# samd21_sensorhub_1_2_5_dec2023.net
KiCad netlist of a schematic drawn in EAGLE
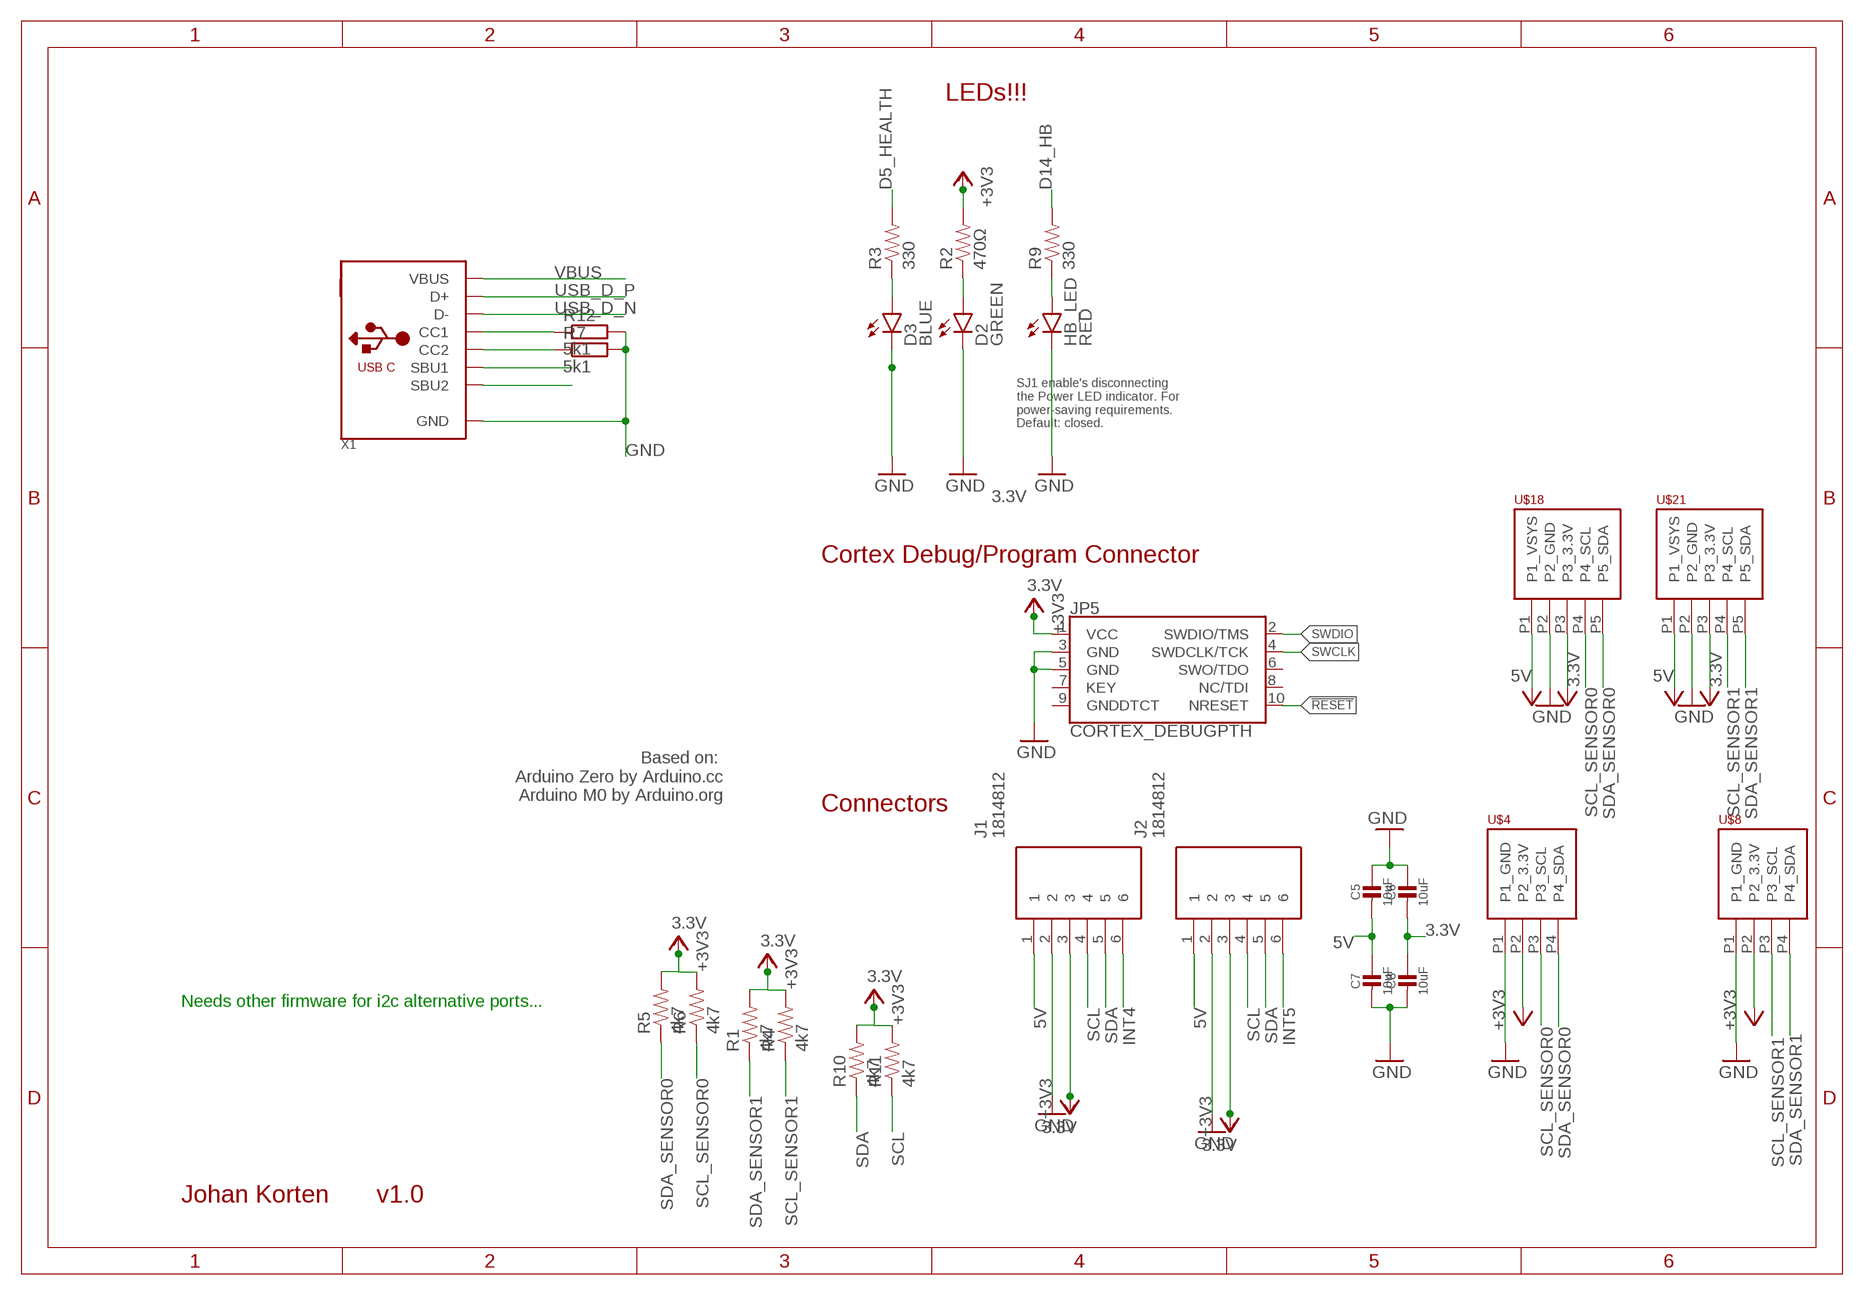
[diagram p0: schematic, sheet 1]
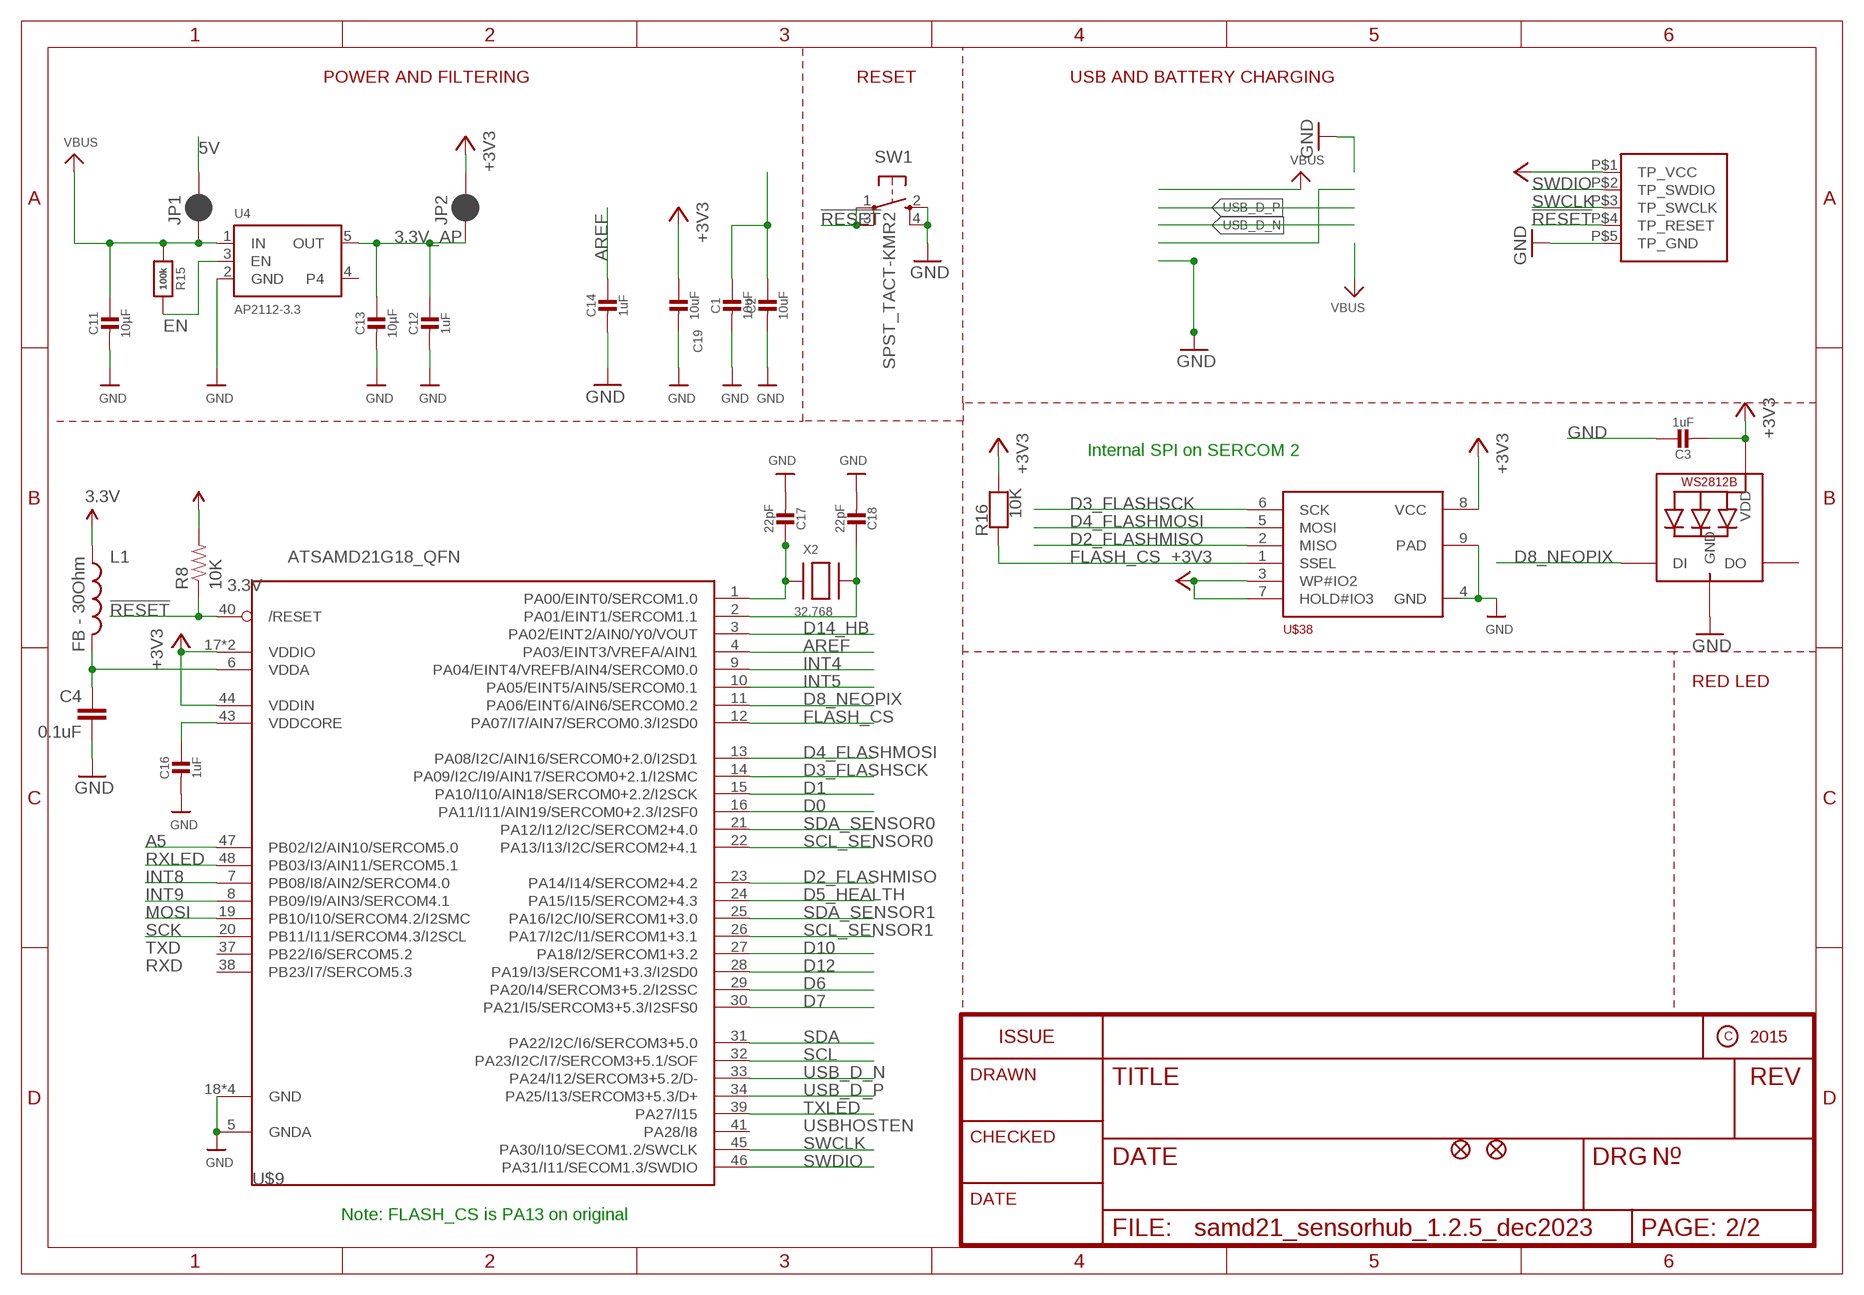
[diagram p1: schematic, sheet 2]

(export (version "E")
  (design (tool "Eeschema 10.0.6"))
  (components
    (comp (ref "C5")
      (value "10uF")
      (footprint "eagle-import:0805-NO")
      (libsource (lib "eagle-import") (part "CAP_CERAMIC0805-NOOUTLINE"))
    )
    (comp (ref "C6")
      (value "10uF")
      (footprint "eagle-import:0805-NO")
      (libsource (lib "eagle-import") (part "CAP_CERAMIC0805-NOOUTLINE"))
    )
    (comp (ref "C7")
      (value "10uF")
      (footprint "eagle-import:0805-NO")
      (libsource (lib "eagle-import") (part "CAP_CERAMIC0805-NOOUTLINE"))
    )
    (comp (ref "C8")
      (value "10uF")
      (footprint "eagle-import:0805-NO")
      (libsource (lib "eagle-import") (part "CAP_CERAMIC0805-NOOUTLINE"))
    )
    (comp (ref "D2")
      (value "GREEN")
      (footprint "eagle-import:LED-0603")
      (libsource (lib "eagle-import") (part "LED-RED0603"))
    )
    (comp (ref "D3")
      (value "BLUE")
      (footprint "eagle-import:LED-0603")
      (libsource (lib "eagle-import") (part "LED-BLUE0603"))
    )
    (comp (ref "HB_LED")
      (value "RED")
      (footprint "eagle-import:LED-0603")
      (libsource (lib "eagle-import") (part "LED-RED0603"))
    )
    (comp (ref "J1")
      (value "1814812")
      (footprint "eagle-import:1814812")
      (fields (field (name "MOUSER_PART_NUMBER") "651-1814812"))
      (libsource (lib "eagle-import") (part "1814812"))
    )
    (comp (ref "J2")
      (value "1814812")
      (footprint "eagle-import:1814812")
      (fields (field (name "MOUSER_PART_NUMBER") "651-1814812"))
      (libsource (lib "eagle-import") (part "1814812"))
    )
    (comp (ref "JP5")
      (value "CORTEX_DEBUGPTH")
      (footprint "eagle-import:2X5-PTH-1.27MM")
      (libsource (lib "eagle-import") (part "CORTEX_DEBUGPTH"))
    )
    (comp (ref "R1")
      (value "4k7")
      (footprint "eagle-import:0603-RES")
      (libsource (lib "eagle-import") (part "330OHM1/10W1%(0603)"))
    )
    (comp (ref "R2")
      (value "470Ω")
      (footprint "eagle-import:0603-RES")
      (libsource (lib "eagle-import") (part "330OHM1/10W1%(0603)"))
    )
    (comp (ref "R3")
      (value "330")
      (footprint "eagle-import:0603-RES")
      (libsource (lib "eagle-import") (part "330OHM1/10W1%(0603)"))
    )
    (comp (ref "R4")
      (value "4k7")
      (footprint "eagle-import:0603-RES")
      (libsource (lib "eagle-import") (part "330OHM1/10W1%(0603)"))
    )
    (comp (ref "R5")
      (value "4k7")
      (footprint "eagle-import:0603-RES")
      (libsource (lib "eagle-import") (part "330OHM1/10W1%(0603)"))
    )
    (comp (ref "R6")
      (value "4k7")
      (footprint "eagle-import:0603-RES")
      (libsource (lib "eagle-import") (part "330OHM1/10W1%(0603)"))
    )
    (comp (ref "R7")
      (value "5k1")
      (footprint "eagle-import:R0603")
      (libsource (lib "eagle-import") (part "R-EU_R0603"))
    )
    (comp (ref "R9")
      (value "330")
      (footprint "eagle-import:0603-RES")
      (libsource (lib "eagle-import") (part "330OHM1/10W1%(0603)"))
    )
    (comp (ref "R10")
      (value "4k7")
      (footprint "eagle-import:0603-RES")
      (libsource (lib "eagle-import") (part "330OHM1/10W1%(0603)"))
    )
    (comp (ref "R11")
      (value "4k7")
      (footprint "eagle-import:0603-RES")
      (libsource (lib "eagle-import") (part "330OHM1/10W1%(0603)"))
    )
    (comp (ref "R12")
      (value "5k1")
      (footprint "eagle-import:R0603")
      (libsource (lib "eagle-import") (part "R-EU_R0603"))
    )
    (comp (ref "U$4")
      (value "PHOENIX_PTSM_M4_THANGLE")
      (footprint "eagle-import:PTSM_M4_TH")
      (libsource (lib "eagle-import") (part "PHOENIX_PTSM_M4_THANGLE"))
    )
    (comp (ref "U$8")
      (value "PHOENIX_PTSM_M4_THANGLE")
      (footprint "eagle-import:PTSM_M4_TH")
      (libsource (lib "eagle-import") (part "PHOENIX_PTSM_M4_THANGLE"))
    )
    (comp (ref "U$18")
      (value "PHOENIX_PTSM_M5_TH_I2C++")
      (footprint "eagle-import:PTSM_M5_THRHOLE")
      (libsource (lib "eagle-import") (part "PHOENIX_PTSM_M5_TH_I2C++"))
    )
    (comp (ref "U$21")
      (value "PHOENIX_PTSM_M5_TH_I2C++")
      (footprint "eagle-import:PTSM_M5_THRHOLE")
      (libsource (lib "eagle-import") (part "PHOENIX_PTSM_M5_TH_I2C++"))
    )
    (comp (ref "X1")
      (value "USB_C")
      (footprint "eagle-import:USB_C_CUSB31-CFM2AX-01-X")
      (libsource (lib "eagle-import") (part "USB_C"))
    )
    (comp (ref "C1")
      (value "10uF")
      (footprint "eagle-import:0805-NO")
      (libsource (lib "eagle-import") (part "CAP_CERAMIC0805-NOOUTLINE"))
    )
    (comp (ref "C2")
      (value "10uF")
      (footprint "eagle-import:0805-NO")
      (libsource (lib "eagle-import") (part "CAP_CERAMIC0805-NOOUTLINE"))
    )
    (comp (ref "C3")
      (value "1uF")
      (footprint "eagle-import:0603-NO")
      (libsource (lib "eagle-import") (part "CAP_CERAMIC0603_NO"))
    )
    (comp (ref "C4")
      (value "0.1uF")
      (footprint "eagle-import:0402-CAP")
      (libsource (lib "eagle-import") (part "0.1UF-16V(+-10%)(0402)"))
    )
    (comp (ref "C11")
      (value "10µF")
      (footprint "eagle-import:0805-NO")
      (libsource (lib "eagle-import") (part "CAP_CERAMIC0805-NOOUTLINE"))
    )
    (comp (ref "C12")
      (value "1uF")
      (footprint "eagle-import:0603-NO")
      (libsource (lib "eagle-import") (part "CAP_CERAMIC0603_NO"))
    )
    (comp (ref "C13")
      (value "10µF")
      (footprint "eagle-import:0805-NO")
      (libsource (lib "eagle-import") (part "CAP_CERAMIC0805-NOOUTLINE"))
    )
    (comp (ref "C14")
      (value "1uF")
      (footprint "eagle-import:0603-NO")
      (libsource (lib "eagle-import") (part "CAP_CERAMIC0603_NO"))
    )
    (comp (ref "C16")
      (value "1uF")
      (footprint "eagle-import:0603-NO")
      (libsource (lib "eagle-import") (part "CAP_CERAMIC0603_NO"))
    )
    (comp (ref "C17")
      (value "22pF")
      (footprint "eagle-import:0603-NO")
      (libsource (lib "eagle-import") (part "CAP_CERAMIC0603_NO"))
    )
    (comp (ref "C18")
      (value "22pF")
      (footprint "eagle-import:0603-NO")
      (libsource (lib "eagle-import") (part "CAP_CERAMIC0603_NO"))
    )
    (comp (ref "C19")
      (value "10uF")
      (footprint "eagle-import:0805-NO")
      (libsource (lib "eagle-import") (part "CAP_CERAMIC0805-NOOUTLINE"))
    )
    (comp (ref "JP1")
      (value "JUMPER-SMT_2_NC_PASTE_SILK")
      (footprint "eagle-import:SMT-JUMPER_2_NC_PASTE_SILK")
      (libsource (lib "eagle-import") (part "JUMPER-SMT_2_NC_PASTE_SILK"))
    )
    (comp (ref "JP2")
      (value "JUMPER-SMT_2_NC_PASTE_SILK")
      (footprint "eagle-import:SMT-JUMPER_2_NC_PASTE_SILK")
      (libsource (lib "eagle-import") (part "JUMPER-SMT_2_NC_PASTE_SILK"))
    )
    (comp (ref "L1")
      (value "FB - 30Ohm")
      (footprint "eagle-import:0603")
      (libsource (lib "eagle-import") (part "INDUCTOR0603"))
    )
    (comp (ref "LED1")
      (value "WS2812B3535")
      (footprint "eagle-import:LED3535")
      (libsource (lib "eagle-import") (part "WS2812B3535"))
    )
    (comp (ref "R8")
      (value "10K")
      (footprint "eagle-import:0603-RES")
      (libsource (lib "eagle-import") (part "10KOHM-1/10W-1%(0603)0603"))
    )
    (comp (ref "R15")
      (value "100k")
      (footprint "eagle-import:0603-NO")
      (libsource (lib "eagle-import") (part "RESISTOR_0603_NOOUT"))
    )
    (comp (ref "R16")
      (value "10K")
      (footprint "eagle-import:0603-NO")
      (libsource (lib "eagle-import") (part "RESISTOR_0603_NOOUT"))
    )
    (comp (ref "SW1")
      (value "SPST_TACT-KMR2")
      (footprint "eagle-import:KMR2")
      (libsource (lib "eagle-import") (part "SPST_TACT-KMR2"))
    )
    (comp (ref "U$5")
      (value "HUB_TESTPINSHUBS")
      (footprint "eagle-import:TEST_PINS")
      (libsource (lib "eagle-import") (part "HUB_TESTPINSHUBS"))
    )
    (comp (ref "U$9")
      (value "ATSAMD21G18_QFN")
      (footprint "eagle-import:TQFN48_7MM")
      (libsource (lib "eagle-import") (part "ATSAMD21G_QFN"))
    )
    (comp (ref "U$34")
      (value "FIDUCIAL\"\"")
      (footprint "eagle-import:FIDUCIAL_1MM")
      (libsource (lib "eagle-import") (part "FIDUCIAL{dblquote}{dblquote}"))
    )
    (comp (ref "U$35")
      (value "FIDUCIAL\"\"")
      (footprint "eagle-import:FIDUCIAL_1MM")
      (libsource (lib "eagle-import") (part "FIDUCIAL{dblquote}{dblquote}"))
    )
    (comp (ref "U$38")
      (value "S25FL064LABNFI040")
      (footprint "eagle-import:SON80P400X400X60-9N")
      (libsource (lib "eagle-import") (part "S25FL064LABNFI040"))
    )
    (comp (ref "U4")
      (value "AP2112-3.3")
      (footprint "eagle-import:SOT23-5")
      (libsource (lib "eagle-import") (part "VREG_SOT23-5"))
    )
    (comp (ref "X2")
      (value "32.768")
      (footprint "eagle-import:XTAL3215")
      (libsource (lib "eagle-import") (part "XTAL-3.2X1.5"))
    )
  )
  (nets
    (net (code "1") (name "3.3V") (class "Default")
      (node (ref "C19") (pin "1") (pinfunction "1_1") (pintype "passive"))
      (node (ref "C3") (pin "2") (pinfunction "2_2") (pintype "passive"))
      (node (ref "C6") (pin "2") (pinfunction "2_2") (pintype "passive"))
      (node (ref "C8") (pin "1") (pinfunction "1_1") (pintype "passive"))
      (node (ref "J1") (pin "3") (pinfunction "3_3") (pintype "bidirectional"))
      (node (ref "J2") (pin "3") (pinfunction "3_3") (pintype "bidirectional"))
      (node (ref "JP2") (pin "2") (pinfunction "2_2") (pintype "passive"))
      (node (ref "JP5") (pin "1") (pinfunction "VCC_1") (pintype "bidirectional"))
      (node (ref "L1") (pin "1") (pinfunction "1_1") (pintype "passive"))
      (node (ref "LED1") (pin "2") (pinfunction "VDD_2") (pintype "power_in"))
      (node (ref "R1") (pin "2") (pinfunction "2_2") (pintype "passive"))
      (node (ref "R10") (pin "2") (pinfunction "2_2") (pintype "passive"))
      (node (ref "R11") (pin "2") (pinfunction "2_2") (pintype "passive"))
      (node (ref "R16") (pin "2") (pinfunction "2_2") (pintype "passive"))
      (node (ref "R2") (pin "2") (pinfunction "2_2") (pintype "passive"))
      (node (ref "R4") (pin "2") (pinfunction "2_2") (pintype "passive"))
      (node (ref "R5") (pin "2") (pinfunction "2_2") (pintype "passive"))
      (node (ref "R6") (pin "2") (pinfunction "2_2") (pintype "passive"))
      (node (ref "R8") (pin "2") (pinfunction "2_2") (pintype "passive"))
      (node (ref "U$18") (pin "P3") (pinfunction "P3_3.3V_P3") (pintype "power_in"))
      (node (ref "U$21") (pin "P3") (pinfunction "P3_3.3V_P3") (pintype "power_in"))
      (node (ref "U$38") (pin "3") (pinfunction "WP#IO2_3") (pintype "bidirectional"))
      (node (ref "U$38") (pin "7") (pinfunction "HOLD#IO3_7") (pintype "bidirectional"))
      (node (ref "U$38") (pin "8") (pinfunction "VCC_8") (pintype "bidirectional"))
      (node (ref "U$4") (pin "P2") (pinfunction "P2_3.3V_P2") (pintype "power_in"))
      (node (ref "U$5") (pin "P$1") (pinfunction "TP_VCC_P$1") (pintype "bidirectional"))
      (node (ref "U$8") (pin "P2") (pinfunction "P2_3.3V_P2") (pintype "power_in"))
      (node (ref "U$9") (pin "17") (pinfunction "VDDIO_17") (pintype "power_in"))
      (node (ref "U$9") (pin "36") (pinfunction "VDDIO_36") (pintype "power_in"))
      (node (ref "U$9") (pin "44") (pinfunction "VDDIN_44") (pintype "power_in"))
    )
    (net (code "2") (name "3.3V_AP") (class "Default")
      (node (ref "C12") (pin "1") (pinfunction "1_1") (pintype "passive"))
      (node (ref "C13") (pin "1") (pinfunction "1_1") (pintype "passive"))
      (node (ref "JP2") (pin "1") (pinfunction "1_1") (pintype "passive"))
      (node (ref "U4") (pin "5") (pinfunction "OUT_5") (pintype "power_in"))
    )
    (net (code "3") (name "5V") (class "Default")
      (node (ref "C1") (pin "1") (pinfunction "1_1") (pintype "passive"))
      (node (ref "C2") (pin "1") (pinfunction "1_1") (pintype "passive"))
      (node (ref "C5") (pin "2") (pinfunction "2_2") (pintype "passive"))
      (node (ref "C7") (pin "1") (pinfunction "1_1") (pintype "passive"))
      (node (ref "J1") (pin "1") (pinfunction "1_1") (pintype "bidirectional"))
      (node (ref "J2") (pin "1") (pinfunction "1_1") (pintype "bidirectional"))
      (node (ref "JP1") (pin "2") (pinfunction "2_2") (pintype "passive"))
      (node (ref "U$18") (pin "P1") (pinfunction "P1_VSYS_P1") (pintype "power_in"))
      (node (ref "U$21") (pin "P1") (pinfunction "P1_VSYS_P1") (pintype "power_in"))
    )
    (net (code "4") (name "A5") (class "Default")
      (node (ref "U$9") (pin "47") (pinfunction "PB02/I2/AIN10/SERCOM5.0_47") (pintype "bidirectional"))
    )
    (net (code "5") (name "AREF") (class "Default")
      (node (ref "C14") (pin "1") (pinfunction "1_1") (pintype "passive"))
      (node (ref "U$9") (pin "4") (pinfunction "PA03/EINT3/VREFA/AIN1_4") (pintype "bidirectional"))
    )
    (net (code "6") (name "D0") (class "Default")
      (node (ref "U$9") (pin "16") (pinfunction "PA11/I11/AIN19/SERCOM0+2.3/I2SF0_16") (pintype "bidirectional"))
    )
    (net (code "7") (name "D1") (class "Default")
      (node (ref "U$9") (pin "15") (pinfunction "PA10/I10/AIN18/SERCOM0+2.2/I2SCK_15") (pintype "bidirectional"))
    )
    (net (code "8") (name "D2_FLASHMISO") (class "Default")
      (node (ref "U$38") (pin "2") (pinfunction "MISO_2") (pintype "bidirectional"))
      (node (ref "U$9") (pin "23") (pinfunction "PA14/I14/SERCOM2+4.2_23") (pintype "bidirectional"))
    )
    (net (code "9") (name "D3_FLASHSCK") (class "Default")
      (node (ref "U$38") (pin "6") (pinfunction "SCK_6") (pintype "bidirectional"))
      (node (ref "U$9") (pin "14") (pinfunction "PA09/I2C/I9/AIN17/SERCOM0+2.1/I2SMC_14") (pintype "bidirectional"))
    )
    (net (code "10") (name "D4_FLASHMOSI") (class "Default")
      (node (ref "U$38") (pin "5") (pinfunction "MOSI_5") (pintype "bidirectional"))
      (node (ref "U$9") (pin "13") (pinfunction "PA08/I2C/AIN16/SERCOM0+2.0/I2SD1_13") (pintype "bidirectional"))
    )
    (net (code "11") (name "D5_HEALTH") (class "Default")
      (node (ref "R3") (pin "2") (pinfunction "2_2") (pintype "passive"))
      (node (ref "U$9") (pin "24") (pinfunction "PA15/I15/SERCOM2+4.3_24") (pintype "bidirectional"))
    )
    (net (code "12") (name "D6") (class "Default")
      (node (ref "U$9") (pin "29") (pinfunction "PA20/I4/SERCOM3+5.2/I2SSC_29") (pintype "bidirectional"))
    )
    (net (code "13") (name "D7") (class "Default")
      (node (ref "U$9") (pin "30") (pinfunction "PA21/I5/SERCOM3+5.3/I2SFS0_30") (pintype "bidirectional"))
    )
    (net (code "14") (name "D8_NEOPIX") (class "Default")
      (node (ref "LED1") (pin "1") (pinfunction "DI_1") (pintype "input"))
      (node (ref "U$9") (pin "11") (pinfunction "PA06/EINT6/AIN6/SERCOM0.2_11") (pintype "bidirectional"))
    )
    (net (code "15") (name "D10") (class "Default")
      (node (ref "U$9") (pin "27") (pinfunction "PA18/I2/SERCOM1+3.2_27") (pintype "bidirectional"))
    )
    (net (code "16") (name "D12") (class "Default")
      (node (ref "U$9") (pin "28") (pinfunction "PA19/I3/SERCOM1+3.3/I2SD0_28") (pintype "bidirectional"))
    )
    (net (code "17") (name "D14_HB") (class "Default")
      (node (ref "R9") (pin "2") (pinfunction "2_2") (pintype "passive"))
      (node (ref "U$9") (pin "3") (pinfunction "PA02/EINT2/AIN0/Y0/VOUT_3") (pintype "bidirectional"))
    )
    (net (code "18") (name "EN") (class "Default")
      (node (ref "R15") (pin "2") (pinfunction "2_2") (pintype "passive"))
      (node (ref "U4") (pin "3") (pinfunction "EN_3") (pintype "input"))
    )
    (net (code "19") (name "FLASH_CS") (class "Default")
      (node (ref "R16") (pin "1") (pinfunction "1_1") (pintype "passive"))
      (node (ref "U$38") (pin "1") (pinfunction "SSEL_1") (pintype "bidirectional"))
      (node (ref "U$9") (pin "12") (pinfunction "PA07/I7/AIN7/SERCOM0.3/I2SD0_12") (pintype "bidirectional"))
    )
    (net (code "20") (name "GND") (class "Default")
      (node (ref "C1") (pin "2") (pinfunction "2_2") (pintype "passive"))
      (node (ref "C11") (pin "2") (pinfunction "2_2") (pintype "passive"))
      (node (ref "C12") (pin "2") (pinfunction "2_2") (pintype "passive"))
      (node (ref "C13") (pin "2") (pinfunction "2_2") (pintype "passive"))
      (node (ref "C14") (pin "2") (pinfunction "2_2") (pintype "passive"))
      (node (ref "C16") (pin "2") (pinfunction "2_2") (pintype "passive"))
      (node (ref "C17") (pin "2") (pinfunction "2_2") (pintype "passive"))
      (node (ref "C18") (pin "2") (pinfunction "2_2") (pintype "passive"))
      (node (ref "C19") (pin "2") (pinfunction "2_2") (pintype "passive"))
      (node (ref "C2") (pin "2") (pinfunction "2_2") (pintype "passive"))
      (node (ref "C3") (pin "1") (pinfunction "1_1") (pintype "passive"))
      (node (ref "C4") (pin "2") (pinfunction "2_2") (pintype "passive"))
      (node (ref "C5") (pin "1") (pinfunction "1_1") (pintype "passive"))
      (node (ref "C6") (pin "1") (pinfunction "1_1") (pintype "passive"))
      (node (ref "C7") (pin "2") (pinfunction "2_2") (pintype "passive"))
      (node (ref "C8") (pin "2") (pinfunction "2_2") (pintype "passive"))
      (node (ref "D2") (pin "C") (pinfunction "C_C") (pintype "passive"))
      (node (ref "D3") (pin "C") (pinfunction "C_C") (pintype "passive"))
      (node (ref "HB_LED") (pin "C") (pinfunction "C_C") (pintype "passive"))
      (node (ref "J1") (pin "2") (pinfunction "2_2") (pintype "bidirectional"))
      (node (ref "J2") (pin "2") (pinfunction "2_2") (pintype "bidirectional"))
      (node (ref "JP5") (pin "3") (pinfunction "GND_3") (pintype "bidirectional"))
      (node (ref "JP5") (pin "5") (pinfunction "GND_5") (pintype "bidirectional"))
      (node (ref "LED1") (pin "4") (pinfunction "GND_4") (pintype "power_in"))
      (node (ref "R12") (pin "2") (pinfunction "2_2") (pintype "passive"))
      (node (ref "R7") (pin "2") (pinfunction "2_2") (pintype "passive"))
      (node (ref "SW1") (pin "2") (pinfunction "S_2") (pintype "passive"))
      (node (ref "SW1") (pin "4") (pinfunction "S1_4") (pintype "passive"))
      (node (ref "U$18") (pin "P2") (pinfunction "P2_GND_P2") (pintype "power_in"))
      (node (ref "U$21") (pin "P2") (pinfunction "P2_GND_P2") (pintype "power_in"))
      (node (ref "U$38") (pin "4") (pinfunction "GND_4") (pintype "bidirectional"))
      (node (ref "U$38") (pin "9") (pinfunction "PAD_9") (pintype "bidirectional"))
      (node (ref "U$4") (pin "P1") (pinfunction "P1_GND_P1") (pintype "power_in"))
      (node (ref "U$5") (pin "P$5") (pinfunction "TP_GND_P$5") (pintype "bidirectional"))
      (node (ref "U$8") (pin "P1") (pinfunction "P1_GND_P1") (pintype "power_in"))
      (node (ref "U$9") (pin "18") (pinfunction "GND_18") (pintype "power_in"))
      (node (ref "U$9") (pin "35") (pinfunction "GND_35") (pintype "power_in"))
      (node (ref "U$9") (pin "42") (pinfunction "GND_42") (pintype "power_in"))
      (node (ref "U$9") (pin "5") (pinfunction "GNDA_5") (pintype "power_in"))
      (node (ref "U$9") (pin "THERMAL") (pinfunction "GND_THERMAL") (pintype "power_in"))
      (node (ref "U4") (pin "2") (pinfunction "GND_2") (pintype "power_in"))
      (node (ref "X1") (pin "A1B12") (pinfunction "GND_A1B12") (pintype "power_in"))
      (node (ref "X1") (pin "B1A12") (pinfunction "GND_B1A12") (pintype "power_in"))
    )
    (net (code "21") (name "INT4") (class "Default")
      (node (ref "J1") (pin "6") (pinfunction "6_6") (pintype "bidirectional"))
      (node (ref "U$9") (pin "9") (pinfunction "PA04/EINT4/VREFB/AIN4/SERCOM0.0_9") (pintype "bidirectional"))
    )
    (net (code "22") (name "INT5") (class "Default")
      (node (ref "J2") (pin "6") (pinfunction "6_6") (pintype "bidirectional"))
      (node (ref "U$9") (pin "10") (pinfunction "PA05/EINT5/AIN5/SERCOM0.1_10") (pintype "bidirectional"))
    )
    (net (code "23") (name "INT8") (class "Default")
      (node (ref "U$9") (pin "7") (pinfunction "PB08/I8/AIN2/SERCOM4.0_7") (pintype "bidirectional"))
    )
    (net (code "24") (name "INT9") (class "Default")
      (node (ref "U$9") (pin "8") (pinfunction "PB09/I9/AIN3/SERCOM4.1_8") (pintype "bidirectional"))
    )
    (net (code "25") (name "MOSI") (class "Default")
      (node (ref "U$9") (pin "19") (pinfunction "PB10/I10/SERCOM4.2/I2SMC_19") (pintype "bidirectional"))
    )
    (net (code "26") (name "Net-(D2-PadA)") (class "Default")
      (node (ref "D2") (pin "A") (pinfunction "A_A") (pintype "passive"))
      (node (ref "R2") (pin "1") (pinfunction "1_1") (pintype "passive"))
    )
    (net (code "27") (name "Net-(D3-PadA)") (class "Default")
      (node (ref "D3") (pin "A") (pinfunction "A_A") (pintype "passive"))
      (node (ref "R3") (pin "1") (pinfunction "1_1") (pintype "passive"))
    )
    (net (code "28") (name "Net-(HB_LED-PadA)") (class "Default")
      (node (ref "HB_LED") (pin "A") (pinfunction "A_A") (pintype "passive"))
      (node (ref "R9") (pin "1") (pinfunction "1_1") (pintype "passive"))
    )
    (net (code "29") (name "Net-(U$9-PA00{slash}EINT0{slash}SERCOM1.0)") (class "Default")
      (node (ref "C17") (pin "1") (pinfunction "1_1") (pintype "passive"))
      (node (ref "U$9") (pin "1") (pinfunction "PA00/EINT0/SERCOM1.0_1") (pintype "bidirectional"))
      (node (ref "X2") (pin "P$1") (pinfunction "P$1_P$1") (pintype "bidirectional"))
    )
    (net (code "30") (name "Net-(U$9-PA01{slash}EINT1{slash}SERCOM1.1)") (class "Default")
      (node (ref "C18") (pin "1") (pinfunction "1_1") (pintype "passive"))
      (node (ref "U$9") (pin "2") (pinfunction "PA01/EINT1/SERCOM1.1_2") (pintype "bidirectional"))
      (node (ref "X2") (pin "P$2") (pinfunction "P$2_P$2") (pintype "bidirectional"))
    )
    (net (code "31") (name "Net-(U$9-VDDA)") (class "Default")
      (node (ref "C4") (pin "1") (pinfunction "1_1") (pintype "passive"))
      (node (ref "L1") (pin "2") (pinfunction "2_2") (pintype "passive"))
      (node (ref "U$9") (pin "6") (pinfunction "VDDA_6") (pintype "power_in"))
    )
    (net (code "32") (name "Net-(U$9-VDDCORE)") (class "Default")
      (node (ref "C16") (pin "1") (pinfunction "1_1") (pintype "passive"))
      (node (ref "U$9") (pin "43") (pinfunction "VDDCORE_43") (pintype "power_in"))
    )
    (net (code "33") (name "Net-(X1-CC1)") (class "Default")
      (node (ref "R12") (pin "1") (pinfunction "1_1") (pintype "passive"))
      (node (ref "X1") (pin "A5") (pinfunction "CC1_A5") (pintype "bidirectional"))
    )
    (net (code "34") (name "Net-(X1-CC2)") (class "Default")
      (node (ref "R7") (pin "1") (pinfunction "1_1") (pintype "passive"))
      (node (ref "X1") (pin "B5") (pinfunction "CC2_B5") (pintype "bidirectional"))
    )
    (net (code "35") (name "RXLED") (class "Default")
      (node (ref "U$9") (pin "48") (pinfunction "PB03/I3/AIN11/SERCOM5.1_48") (pintype "bidirectional"))
    )
    (net (code "36") (name "SCK") (class "Default")
      (node (ref "U$9") (pin "20") (pinfunction "PB11/I11/SERCOM4.3/I2SCL_20") (pintype "bidirectional"))
    )
    (net (code "37") (name "SCL") (class "Default")
      (node (ref "J1") (pin "4") (pinfunction "4_4") (pintype "bidirectional"))
      (node (ref "J2") (pin "4") (pinfunction "4_4") (pintype "bidirectional"))
      (node (ref "R11") (pin "1") (pinfunction "1_1") (pintype "passive"))
      (node (ref "U$9") (pin "32") (pinfunction "PA23/I2C/I7/SERCOM3+5.1/SOF_32") (pintype "bidirectional"))
    )
    (net (code "38") (name "SCL_SENSOR0") (class "Default")
      (node (ref "R6") (pin "1") (pinfunction "1_1") (pintype "passive"))
      (node (ref "U$18") (pin "P4") (pinfunction "P4_SCL_P4") (pintype "bidirectional"))
      (node (ref "U$4") (pin "P3") (pinfunction "P3_SCL_P3") (pintype "bidirectional"))
      (node (ref "U$9") (pin "22") (pinfunction "PA13/I13/I2C/SERCOM2+4.1_22") (pintype "bidirectional"))
    )
    (net (code "39") (name "SCL_SENSOR1") (class "Default")
      (node (ref "R4") (pin "1") (pinfunction "1_1") (pintype "passive"))
      (node (ref "U$21") (pin "P4") (pinfunction "P4_SCL_P4") (pintype "bidirectional"))
      (node (ref "U$8") (pin "P3") (pinfunction "P3_SCL_P3") (pintype "bidirectional"))
      (node (ref "U$9") (pin "26") (pinfunction "PA17/I2C/I1/SERCOM1+3.1_26") (pintype "bidirectional"))
    )
    (net (code "40") (name "SDA") (class "Default")
      (node (ref "J1") (pin "5") (pinfunction "5_5") (pintype "bidirectional"))
      (node (ref "J2") (pin "5") (pinfunction "5_5") (pintype "bidirectional"))
      (node (ref "R10") (pin "1") (pinfunction "1_1") (pintype "passive"))
      (node (ref "U$9") (pin "31") (pinfunction "PA22/I2C/I6/SERCOM3+5.0_31") (pintype "bidirectional"))
    )
    (net (code "41") (name "SDA_SENSOR0") (class "Default")
      (node (ref "R5") (pin "1") (pinfunction "1_1") (pintype "passive"))
      (node (ref "U$18") (pin "P5") (pinfunction "P5_SDA_P5") (pintype "bidirectional"))
      (node (ref "U$4") (pin "P4") (pinfunction "P4_SDA_P4") (pintype "bidirectional"))
      (node (ref "U$9") (pin "21") (pinfunction "PA12/I12/I2C/SERCOM2+4.0_21") (pintype "bidirectional"))
    )
    (net (code "42") (name "SDA_SENSOR1") (class "Default")
      (node (ref "R1") (pin "1") (pinfunction "1_1") (pintype "passive"))
      (node (ref "U$21") (pin "P5") (pinfunction "P5_SDA_P5") (pintype "bidirectional"))
      (node (ref "U$8") (pin "P4") (pinfunction "P4_SDA_P4") (pintype "bidirectional"))
      (node (ref "U$9") (pin "25") (pinfunction "PA16/I2C/I0/SERCOM1+3.0_25") (pintype "bidirectional"))
    )
    (net (code "43") (name "SWCLK") (class "Default")
      (node (ref "JP5") (pin "4") (pinfunction "SWDCLK/TCK_4") (pintype "bidirectional"))
      (node (ref "U$5") (pin "P$3") (pinfunction "TP_SWCLK_P$3") (pintype "bidirectional"))
      (node (ref "U$9") (pin "45") (pinfunction "PA30/I10/SECOM1.2/SWCLK_45") (pintype "bidirectional"))
    )
    (net (code "44") (name "SWDIO") (class "Default")
      (node (ref "JP5") (pin "2") (pinfunction "SWDIO/TMS_2") (pintype "bidirectional"))
      (node (ref "U$5") (pin "P$2") (pinfunction "TP_SWDIO_P$2") (pintype "bidirectional"))
      (node (ref "U$9") (pin "46") (pinfunction "PA31/I11/SECOM1.3/SWDIO_46") (pintype "bidirectional"))
    )
    (net (code "45") (name "TXLED") (class "Default")
      (node (ref "U$9") (pin "39") (pinfunction "PA27/I15_39") (pintype "bidirectional"))
    )
    (net (code "46") (name "USB_D_N") (class "Default")
      (node (ref "U$9") (pin "33") (pinfunction "PA24/I12/SERCOM3+5.2/D-_33") (pintype "bidirectional"))
      (node (ref "X1") (pin "A7") (pinfunction "D-_A7") (pintype "bidirectional"))
      (node (ref "X1") (pin "B7") (pinfunction "D-_B7") (pintype "bidirectional"))
    )
    (net (code "47") (name "USB_D_P") (class "Default")
      (node (ref "U$9") (pin "34") (pinfunction "PA25/I13/SERCOM3+5.3/D+_34") (pintype "bidirectional"))
      (node (ref "X1") (pin "A6") (pinfunction "D+_A6") (pintype "bidirectional"))
      (node (ref "X1") (pin "B6") (pinfunction "D+_B6") (pintype "bidirectional"))
    )
    (net (code "48") (name "VBUS") (class "Default")
      (node (ref "C11") (pin "1") (pinfunction "1_1") (pintype "passive"))
      (node (ref "JP1") (pin "1") (pinfunction "1_1") (pintype "passive"))
      (node (ref "R15") (pin "1") (pinfunction "1_1") (pintype "passive"))
      (node (ref "U4") (pin "1") (pinfunction "IN_1") (pintype "power_in"))
      (node (ref "X1") (pin "A4B9") (pinfunction "VBUS_A4B9") (pintype "power_in"))
      (node (ref "X1") (pin "B4A9") (pinfunction "VBUS_B4A9") (pintype "power_in"))
    )
    (net (code "49") (name "unconnected-(JP5-GNDDTCT-Pad9)") (class "Default")
      (node (ref "JP5") (pin "9") (pinfunction "GNDDTCT_9") (pintype "bidirectional"))
    )
    (net (code "50") (name "unconnected-(JP5-KEY-Pad7)") (class "Default")
      (node (ref "JP5") (pin "7") (pinfunction "KEY_7") (pintype "bidirectional"))
    )
    (net (code "51") (name "unconnected-(JP5-NC{slash}TDI-Pad8)") (class "Default")
      (node (ref "JP5") (pin "8") (pinfunction "NC/TDI_8") (pintype "bidirectional"))
    )
    (net (code "52") (name "unconnected-(JP5-SWO{slash}TDO-Pad6)") (class "Default")
      (node (ref "JP5") (pin "6") (pinfunction "SWO/TDO_6") (pintype "bidirectional"))
    )
    (net (code "53") (name "unconnected-(LED1-DO-Pad3)") (class "Default")
      (node (ref "LED1") (pin "3") (pinfunction "DO_3") (pintype "output"))
    )
    (net (code "54") (name "unconnected-(U$9-PA28{slash}I8-Pad41)") (class "Default")
      (node (ref "U$9") (pin "41") (pinfunction "PA28/I8_41") (pintype "bidirectional"))
    )
    (net (code "55") (name "unconnected-(U$9-PB22{slash}I6{slash}SERCOM5.2-Pad37)") (class "Default")
      (node (ref "U$9") (pin "37") (pinfunction "PB22/I6/SERCOM5.2_37") (pintype "bidirectional"))
    )
    (net (code "56") (name "unconnected-(U$9-PB23{slash}I7{slash}SERCOM5.3-Pad38)") (class "Default")
      (node (ref "U$9") (pin "38") (pinfunction "PB23/I7/SERCOM5.3_38") (pintype "bidirectional"))
    )
    (net (code "57") (name "unconnected-(U4-P4-Pad4)") (class "Default")
      (node (ref "U4") (pin "4") (pinfunction "P4_4") (pintype "bidirectional"))
    )
    (net (code "58") (name "unconnected-(X1-SBU1-PadA8)") (class "Default")
      (node (ref "X1") (pin "A8") (pinfunction "SBU1_A8") (pintype "bidirectional"))
    )
    (net (code "59") (name "unconnected-(X1-SBU2-PadB8)") (class "Default")
      (node (ref "X1") (pin "B8") (pinfunction "SBU2_B8") (pintype "bidirectional"))
    )
    (net (code "60") (name "~{RESET}") (class "Default")
      (node (ref "JP5") (pin "10") (pinfunction "NRESET_10") (pintype "bidirectional"))
      (node (ref "R8") (pin "1") (pinfunction "1_1") (pintype "passive"))
      (node (ref "SW1") (pin "1") (pinfunction "P_1") (pintype "passive"))
      (node (ref "SW1") (pin "3") (pinfunction "P1_3") (pintype "passive"))
      (node (ref "U$5") (pin "P$4") (pinfunction "TP_RESET_P$4") (pintype "bidirectional"))
      (node (ref "U$9") (pin "40") (pinfunction "/RESET_40") (pintype "bidirectional"))
    )
  )
)
